# design.net
KiCad netlist of a schematic drawn in Altium Designer
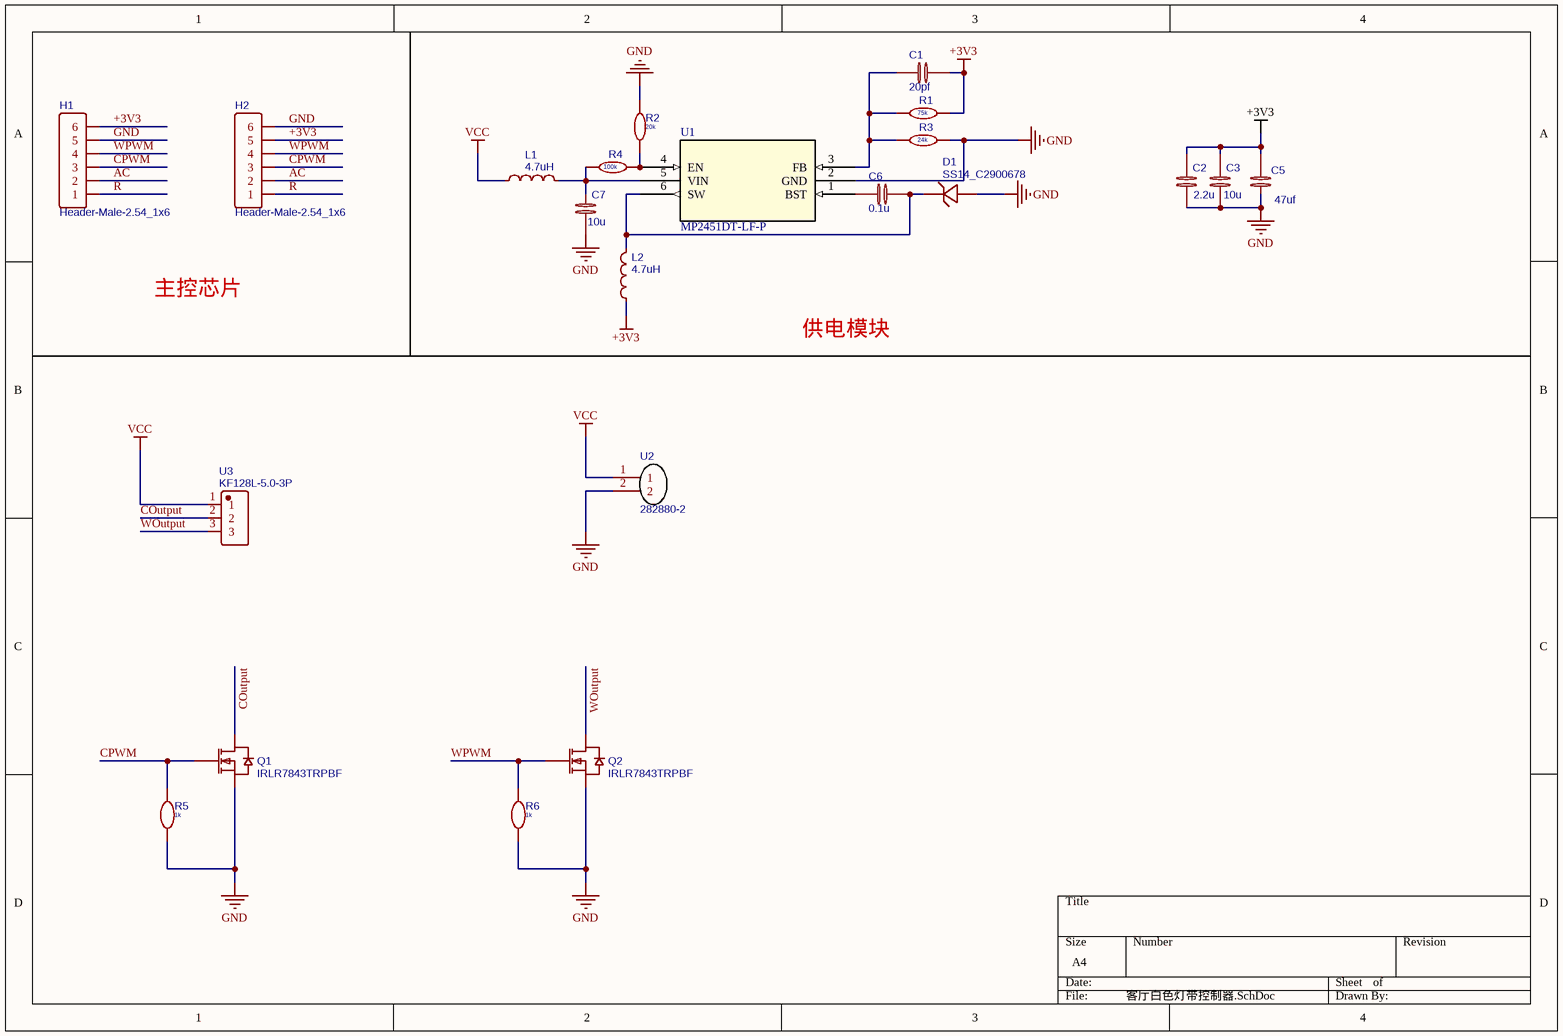
[diagram p0: 客厅白色灯带控制器.SchDoc]

(export (version "E")
  (design (tool "Eeschema 10.0.6"))
  (components
    (comp (ref "C1")
      (value "20pf")
      (footprint "C0603")
      (fields (field (name "CONTRIBUTOR") "LCEDA_Lib"))
      (libsource (lib "altium-import") (part "root_0_0.1u_"))
    )
    (comp (ref "C2")
      (value "2.2u")
      (footprint "C0603")
      (fields (field (name "CONTRIBUTOR") "LCEDA_Lib"))
      (libsource (lib "altium-import") (part "root_1_2.2u_"))
    )
    (comp (ref "C3")
      (value "10u")
      (footprint "C0603")
      (fields (field (name "CONTRIBUTOR") "LCEDA_Lib"))
      (libsource (lib "altium-import") (part "root_1_10u_"))
    )
    (comp (ref "C5")
      (value "47uf")
      (footprint "C0603")
      (fields (field (name "CONTRIBUTOR") "LCEDA_Lib"))
      (libsource (lib "altium-import") (part "root_1_0.1u_"))
    )
    (comp (ref "C6")
      (value "0.1u")
      (footprint "C0603")
      (fields (field (name "CONTRIBUTOR") "LCEDA_Lib"))
      (libsource (lib "altium-import") (part "root_0_0.1u_"))
    )
    (comp (ref "C7")
      (value "10u")
      (footprint "C0603")
      (fields (field (name "CONTRIBUTOR") "LCEDA_Lib"))
      (libsource (lib "altium-import") (part "root_1_0.1u_"))
    )
    (comp (ref "D1")
      (value "SS14_C2900678")
      (footprint "SMA_L4.3-W2.5-LS5.0-RD-1")
      (fields
        (field (name "BOM_SUPPLIER PART") "C2900678")
        (field (name "BOM_MANUFACTURER PART") "SS14")
        (field (name "CONTRIBUTOR") "LCSC")
      )
      (libsource (lib "altium-import") (part "root_0_SS14_C2900678_"))
    )
    (comp (ref "H1")
      (value "Header-Male-2.54_1x6")
      (footprint "HDR-TH_6P-P2.54-V-M-1")
      (fields (field (name "BOM_SUPPLIER PART") "C37208"))
      (libsource (lib "altium-import") (part "root_2_Header-Male-2.54_1x6_"))
    )
    (comp (ref "H2")
      (value "Header-Male-2.54_1x6")
      (footprint "HDR-TH_6P-P2.54-V-M-1")
      (fields (field (name "BOM_SUPPLIER PART") "C37208"))
      (libsource (lib "altium-import") (part "root_2_Header-Male-2.54_1x6_"))
    )
    (comp (ref "L1")
      (value "4.7uH")
      (footprint "L1008")
      (fields
        (field (name "BOM_MANUFACTURER PART") "SMMS0630-4R7M")
        (field (name "BOM_SUPPLIER PART") "C128688")
      )
      (libsource (lib "altium-import") (part "root_0_4.7uH_"))
    )
    (comp (ref "L2")
      (value "4.7uH")
      (footprint "L1008")
      (fields
        (field (name "BOM_MANUFACTURER PART") "SMMS0630-4R7M")
        (field (name "BOM_SUPPLIER PART") "C128688")
      )
      (libsource (lib "altium-import") (part "root_1_4.7uH_"))
    )
    (comp (ref "Q1")
      (value "IRLR7843TRPBF")
      (footprint "TO-252-2_L6.5-W6.1-P4.58-LS10.0-TR")
      (fields (field (name "BOM_SUPPLIER PART") "C21988"))
      (libsource (lib "altium-import") (part "root_0_IRLR7843TRPBF_"))
    )
    (comp (ref "Q2")
      (value "IRLR7843TRPBF")
      (footprint "TO-252-2_L6.5-W6.1-P4.58-LS10.0-TR")
      (fields (field (name "BOM_SUPPLIER PART") "C21988"))
      (libsource (lib "altium-import") (part "root_0_IRLR7843TRPBF_"))
    )
    (comp (ref "R1")
      (value "75k")
      (footprint "R0603")
      (fields
        (field (name "BOM_MANUFACTURER PART") "CRCW060310K0JNEA")
        (field (name "BOM_SUPPLIER PART") "C169103")
      )
      (libsource (lib "altium-import") (part "root_0_10k_"))
    )
    (comp (ref "R2")
      (value "20k")
      (footprint "R0603")
      (fields
        (field (name "BOM_MANUFACTURER PART") "CRCW060310K0JNEA")
        (field (name "BOM_SUPPLIER PART") "C169103")
      )
      (libsource (lib "altium-import") (part "root_1_10k_"))
    )
    (comp (ref "R3")
      (value "24k")
      (footprint "R0603")
      (fields
        (field (name "BOM_MANUFACTURER PART") "CRCW060310K0JNEA")
        (field (name "BOM_SUPPLIER PART") "C169103")
      )
      (libsource (lib "altium-import") (part "root_0_10k_"))
    )
    (comp (ref "R4")
      (value "100k")
      (footprint "R0603")
      (fields
        (field (name "BOM_MANUFACTURER PART") "CRCW060310K0JNEA")
        (field (name "BOM_SUPPLIER PART") "C169103")
      )
      (libsource (lib "altium-import") (part "root_0_10k_"))
    )
    (comp (ref "R5")
      (value "1k")
      (footprint "R0603")
      (fields (field (name "CONTRIBUTOR") "LCEDA_Lib"))
      (libsource (lib "altium-import") (part "root_3_NC_"))
    )
    (comp (ref "R6")
      (value "1k")
      (footprint "R0603")
      (fields (field (name "CONTRIBUTOR") "LCEDA_Lib"))
      (libsource (lib "altium-import") (part "root_3_NC_"))
    )
    (comp (ref "U1")
      (value "MP2451DT-LF-P")
      (footprint "SOT-23-6_L2.9-W1.6-P0.95-LS2.8-BR")
      (description "No Description Available")
      (fields (field (name "COPYRIGHT") "Copyright (C) 2022 Ultra Librarian. All rights reserved."))
      (libsource (lib "MP2451DT-LF-P") (part "MP2451DT-LF-P"))
    )
    (comp (ref "U2")
      (value "282880-2")
      (footprint "CONN-TH_2P-P5.00_282880-2")
      (fields (field (name "BOM_SUPPLIER PART") "C306188") (field (name "CONTRIBUTOR") "LCSC"))
      (libsource (lib "altium-import") (part "root_3_282880-2_"))
    )
    (comp (ref "U3")
      (value "KF128L-5.0-3P")
      (footprint "CONN-TH_3P-P5.00_KF128L-5.0-3P")
      (fields (field (name "BOM_SUPPLIER PART") "C474939") (field (name "CONTRIBUTOR") "LCSC"))
      (libsource (lib "altium-import") (part "root_0_KF128L-5.0-3P_"))
    )
  )
  (nets
    (net (code "1") (name "+3V3") (class "Default")
      (node (ref "C1") (pin "2") (pinfunction "2_2") (pintype "passive"))
      (node (ref "C2") (pin "2") (pinfunction "2_2") (pintype "passive"))
      (node (ref "C3") (pin "2") (pinfunction "2_2") (pintype "passive"))
      (node (ref "C5") (pin "2") (pinfunction "2_2") (pintype "passive"))
      (node (ref "H1") (pin "6") (pinfunction "6_6") (pintype "passive"))
      (node (ref "H2") (pin "5") (pinfunction "5_5") (pintype "passive"))
      (node (ref "L2") (pin "1") (pinfunction "1_1") (pintype "passive"))
      (node (ref "R1") (pin "1") (pinfunction "1_1") (pintype "passive"))
    )
    (net (code "2") (name "/AC") (class "Default")
      (node (ref "H1") (pin "2") (pinfunction "2_2") (pintype "passive"))
      (node (ref "H2") (pin "2") (pinfunction "2_2") (pintype "passive"))
    )
    (net (code "3") (name "/COutput") (class "Default")
      (node (ref "Q1") (pin "4") (pinfunction "D_4") (pintype "passive"))
      (node (ref "U3") (pin "2") (pinfunction "2_2") (pintype "passive"))
    )
    (net (code "4") (name "/CPWM") (class "Default")
      (node (ref "H1") (pin "3") (pinfunction "3_3") (pintype "passive"))
      (node (ref "H2") (pin "3") (pinfunction "3_3") (pintype "passive"))
      (node (ref "Q1") (pin "1") (pinfunction "G_1") (pintype "passive"))
      (node (ref "R5") (pin "1") (pinfunction "1_1") (pintype "passive"))
    )
    (net (code "5") (name "/R") (class "Default")
      (node (ref "H1") (pin "1") (pinfunction "1_1") (pintype "passive"))
      (node (ref "H2") (pin "1") (pinfunction "1_1") (pintype "passive"))
    )
    (net (code "6") (name "/WOutput") (class "Default")
      (node (ref "Q2") (pin "4") (pinfunction "D_4") (pintype "passive"))
      (node (ref "U3") (pin "3") (pinfunction "3_3") (pintype "passive"))
    )
    (net (code "7") (name "/WPWM") (class "Default")
      (node (ref "H1") (pin "4") (pinfunction "4_4") (pintype "passive"))
      (node (ref "H2") (pin "4") (pinfunction "4_4") (pintype "passive"))
      (node (ref "Q2") (pin "1") (pinfunction "G_1") (pintype "passive"))
      (node (ref "R6") (pin "1") (pinfunction "1_1") (pintype "passive"))
    )
    (net (code "8") (name "GND") (class "Default")
      (node (ref "C2") (pin "1") (pinfunction "1_1") (pintype "passive"))
      (node (ref "C3") (pin "1") (pinfunction "1_1") (pintype "passive"))
      (node (ref "C5") (pin "1") (pinfunction "1_1") (pintype "passive"))
      (node (ref "C7") (pin "1") (pinfunction "1_1") (pintype "passive"))
      (node (ref "D1") (pin "2") (pinfunction "A_2") (pintype "passive"))
      (node (ref "H1") (pin "5") (pinfunction "5_5") (pintype "passive"))
      (node (ref "H2") (pin "6") (pinfunction "6_6") (pintype "passive"))
      (node (ref "Q1") (pin "3") (pinfunction "S_3") (pintype "passive"))
      (node (ref "Q2") (pin "3") (pinfunction "S_3") (pintype "passive"))
      (node (ref "R2") (pin "1") (pinfunction "1_1") (pintype "passive"))
      (node (ref "R3") (pin "1") (pinfunction "1_1") (pintype "passive"))
      (node (ref "R5") (pin "2") (pinfunction "2_2") (pintype "passive"))
      (node (ref "R6") (pin "2") (pinfunction "2_2") (pintype "passive"))
      (node (ref "U1") (pin "2") (pinfunction "GND_2") (pintype "passive"))
      (node (ref "U2") (pin "2") (pinfunction "2_2") (pintype "passive"))
    )
    (net (code "9") (name "Net-(D1-C)") (class "Default")
      (node (ref "C6") (pin "2") (pinfunction "2_2") (pintype "passive"))
      (node (ref "D1") (pin "1") (pinfunction "C_1") (pintype "passive"))
      (node (ref "L2") (pin "2") (pinfunction "2_2") (pintype "passive"))
      (node (ref "U1") (pin "6") (pinfunction "SW_6") (pintype "output"))
    )
    (net (code "10") (name "Net-(U1-BST)") (class "Default")
      (node (ref "C6") (pin "1") (pinfunction "1_1") (pintype "passive"))
      (node (ref "U1") (pin "1") (pinfunction "BST_1") (pintype "input"))
    )
    (net (code "11") (name "Net-(U1-EN)") (class "Default")
      (node (ref "R2") (pin "2") (pinfunction "2_2") (pintype "passive"))
      (node (ref "R4") (pin "1") (pinfunction "1_1") (pintype "passive"))
      (node (ref "U1") (pin "4") (pinfunction "EN_4") (pintype "input"))
    )
    (net (code "12") (name "Net-(U1-FB)") (class "Default")
      (node (ref "C1") (pin "1") (pinfunction "1_1") (pintype "passive"))
      (node (ref "R1") (pin "2") (pinfunction "2_2") (pintype "passive"))
      (node (ref "R3") (pin "2") (pinfunction "2_2") (pintype "passive"))
      (node (ref "U1") (pin "3") (pinfunction "FB_3") (pintype "input"))
    )
    (net (code "13") (name "Net-(U1-VIN)") (class "Default")
      (node (ref "C7") (pin "2") (pinfunction "2_2") (pintype "passive"))
      (node (ref "L1") (pin "2") (pinfunction "2_2") (pintype "passive"))
      (node (ref "R4") (pin "2") (pinfunction "2_2") (pintype "passive"))
      (node (ref "U1") (pin "5") (pinfunction "VIN_5") (pintype "power_in"))
    )
    (net (code "14") (name "VCC") (class "Default")
      (node (ref "L1") (pin "1") (pinfunction "1_1") (pintype "passive"))
      (node (ref "U2") (pin "1") (pinfunction "1_1") (pintype "passive"))
      (node (ref "U3") (pin "1") (pinfunction "1_1") (pintype "passive"))
    )
  )
)
